# Sensor-Flash.net
KiCad netlist of a schematic drawn in Altium Designer
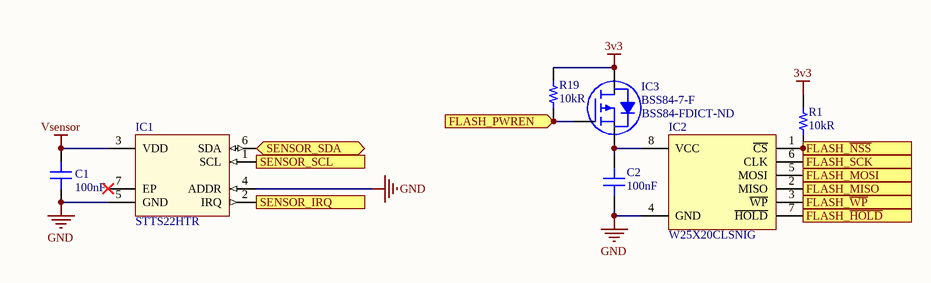
[diagram p0: Sensor-Flash.SchDoc]

(export (version "E")
  (design (tool "Eeschema 10.0.6"))
  (components
    (comp (ref "C1")
      (value "100nF")
      (footprint "CAP 0603/1608")
      (description "Ceramic, SMT Capacitor")
      (fields
        (field (name "MANUFACTURER") "Samsung")
        (field (name "MANUFACTURER PART NUMBER") "CL10B104JB8NNNC")
      )
      (libsource (lib "yildizIoT Library") (part "Capacitor - Ceramic"))
    )
    (comp (ref "C2")
      (value "100nF")
      (footprint "CAP 0603/1608")
      (description "Ceramic, SMT Capacitor")
      (fields
        (field (name "MANUFACTURER") "Samsung")
        (field (name "MANUFACTURER PART NUMBER") "CL10B104JB8NNNC")
      )
      (libsource (lib "yildizIoT Library") (part "Capacitor - Ceramic"))
    )
    (comp (ref "IC1")
      (value "STTS22HTR")
      (footprint "ST UDFN-6 2x2x0.5")
      (description "Low-voltage, ultra-low-power, 0.5 °C accuracy I²C/SMBus 3.0 temperature sensor")
      (fields (field (name "MOUSER PART NUMBER") "511-STTS22HTR") (field (name "RS PART NUMBER") "1947647P"))
      (libsource (lib "yildizIoT Library") (part "ST STTS22HTR"))
    )
    (comp (ref "IC2")
      (value "W25X20CLSNIG")
      (footprint "WINBOND SOIC-8 208MIL WIDE")
      (fields (field (name "MANUFACTURER") "Winbond"))
      (libsource (lib "yildizIoT Library") (part "WINBOND FLASH SPI 8PIN"))
    )
    (comp (ref "IC3")
      (value "BSS84-7-F")
      (footprint "DIODES SOT-23-3")
      (description "DIODES INC. - BSS84-7-F - MOSFET Transistor, P Channel, 130 mA, -50 V, 10 ohm, -5 V, -800 mV")
      (fields (field (name "SUPPLIER PART NUMBER 1") "BSS84-FDICT-ND") (field (name "MANUFACTURER") "Diodes"))
      (libsource (lib "Celestial Altium Library - altium_library") (part "DIODES MOSFET P-CH SOT-23-3"))
    )
    (comp (ref "R1")
      (value "10kR")
      (footprint "RES 0603/1608")
      (description "Ceramic, SMT Capacitor")
      (fields
        (field (name "MANUFACTURER") "Stackpole Electronics")
        (field (name "MANUFACTURER PART NUMBER") "RNCP0603FTD10K0")
      )
      (libsource (lib "yildizIoT Library") (part "Resistor_Chip"))
    )
    (comp (ref "R19")
      (value "10kR")
      (footprint "RES 0603/1608")
      (description "Ceramic, SMT Capacitor")
      (fields
        (field (name "MANUFACTURER") "Stackpole Electronics")
        (field (name "MANUFACTURER PART NUMBER") "RNCP0603FTD10K0")
      )
      (libsource (lib "yildizIoT Library") (part "Resistor_Chip"))
    )
  )
  (nets
    (net (code "1") (name "/FLASH_MISO") (class "Default")
      (node (ref "IC2") (pin "2") (pinfunction "MISO_2") (pintype "passive"))
    )
    (net (code "2") (name "/FLASH_MOSI") (class "Default")
      (node (ref "IC2") (pin "5") (pinfunction "MOSI_5") (pintype "passive"))
    )
    (net (code "3") (name "/FLASH_PWREN") (class "Default")
      (node (ref "IC3") (pin "1") (pinfunction "G_1") (pintype "passive"))
      (node (ref "R19") (pin "1") (pinfunction "1_1") (pintype "passive"))
    )
    (net (code "4") (name "/FLASH_SCK") (class "Default")
      (node (ref "IC2") (pin "6") (pinfunction "CLK_6") (pintype "passive"))
    )
    (net (code "5") (name "/FLASH_~{HOLD}") (class "Default")
      (node (ref "IC2") (pin "7") (pinfunction "~{HOLD}_7") (pintype "passive"))
    )
    (net (code "6") (name "/FLASH_~{NSS}") (class "Default")
      (node (ref "IC2") (pin "1") (pinfunction "~{CS}_1") (pintype "passive"))
      (node (ref "R1") (pin "1") (pinfunction "1_1") (pintype "passive"))
    )
    (net (code "7") (name "/FLASH_~{WP}") (class "Default")
      (node (ref "IC2") (pin "3") (pinfunction "~{WP}_3") (pintype "passive"))
    )
    (net (code "8") (name "/SENSOR_IRQ") (class "Default")
      (node (ref "IC1") (pin "2") (pinfunction "IRQ_2") (pintype "output"))
    )
    (net (code "9") (name "/SENSOR_SCL") (class "Default")
      (node (ref "IC1") (pin "1") (pinfunction "SCL_1") (pintype "input"))
    )
    (net (code "10") (name "/SENSOR_SDA") (class "Default")
      (node (ref "IC1") (pin "6") (pinfunction "SDA_6") (pintype "bidirectional"))
    )
    (net (code "11") (name "3v3") (class "Default")
      (node (ref "IC3") (pin "3") (pinfunction "D_3") (pintype "passive"))
      (node (ref "R1") (pin "2") (pinfunction "2_2") (pintype "passive"))
      (node (ref "R19") (pin "2") (pinfunction "2_2") (pintype "passive"))
    )
    (net (code "12") (name "GND") (class "Default")
      (node (ref "C1") (pin "1") (pinfunction "1_1") (pintype "passive"))
      (node (ref "C2") (pin "2") (pinfunction "2_2") (pintype "passive"))
      (node (ref "IC1") (pin "4") (pinfunction "ADDR_4") (pintype "input"))
      (node (ref "IC1") (pin "5") (pinfunction "GND_5") (pintype "power_in"))
      (node (ref "IC2") (pin "4") (pinfunction "GND_4") (pintype "passive"))
    )
    (net (code "13") (name "Net-(IC2-VCC)") (class "Default")
      (node (ref "C2") (pin "1") (pinfunction "1_1") (pintype "passive"))
      (node (ref "IC2") (pin "8") (pinfunction "VCC_8") (pintype "passive"))
      (node (ref "IC3") (pin "2") (pinfunction "S_2") (pintype "passive"))
    )
    (net (code "14") (name "Vsensor") (class "Default")
      (node (ref "C1") (pin "2") (pinfunction "2_2") (pintype "passive"))
      (node (ref "IC1") (pin "3") (pinfunction "VDD_3") (pintype "power_in"))
    )
    (net (code "15") (name "unconnected-(IC1-EP-Pad7)") (class "Default")
      (node (ref "IC1") (pin "7") (pinfunction "EP_7") (pintype "power_in+no_connect"))
    )
  )
)
